# U.net
KiCad netlist of a schematic drawn in EAGLE
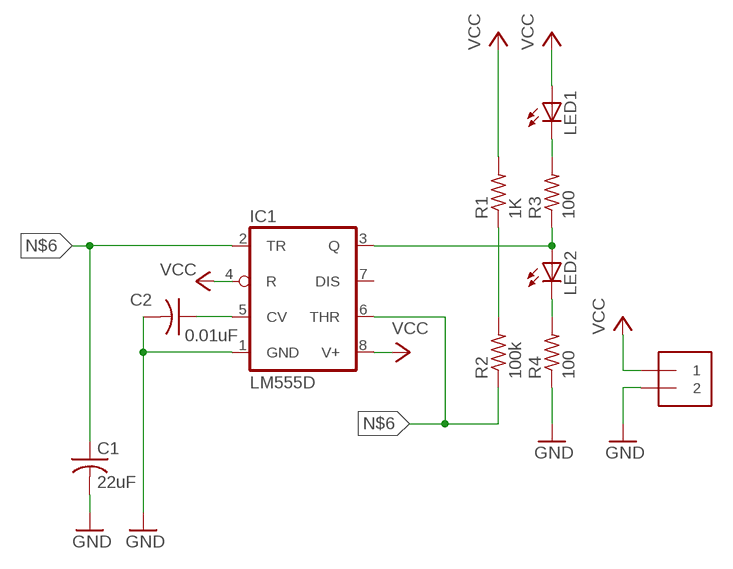
[diagram p0: schematic, sheet 1]

(export (version "E")
  (design (tool "Eeschema 10.0.6"))
  (components
    (comp (ref "C1")
      (value "22uF")
      (footprint "eagle-import:C0805")
      (libsource (lib "eagle-import") (part "C-USC0805"))
    )
    (comp (ref "C2")
      (value "0.01uF")
      (footprint "eagle-import:C0805")
      (libsource (lib "eagle-import") (part "C-USC0805"))
    )
    (comp (ref "IC1")
      (value "LM555D")
      (footprint "eagle-import:SO08")
      (libsource (lib "eagle-import") (part "555DLM"))
    )
    (comp (ref "J1")
      (value "1X2-3.5MM")
      (footprint "eagle-import:1X2-3.5MM")
      (libsource (lib "eagle-import") (part "1X2-3.5MM"))
    )
    (comp (ref "LED1")
      (value "LEDCHIPLED_0805")
      (footprint "eagle-import:CHIPLED_0805")
      (libsource (lib "eagle-import") (part "LEDCHIPLED_0805"))
    )
    (comp (ref "LED2")
      (value "LEDCHIPLED_0805")
      (footprint "eagle-import:CHIPLED_0805")
      (libsource (lib "eagle-import") (part "LEDCHIPLED_0805"))
    )
    (comp (ref "R1")
      (value "1K")
      (footprint "eagle-import:R0805")
      (libsource (lib "eagle-import") (part "R-US_R0805"))
    )
    (comp (ref "R2")
      (value "100k")
      (footprint "eagle-import:R0805")
      (libsource (lib "eagle-import") (part "R-US_R0805"))
    )
    (comp (ref "R3")
      (value "100")
      (footprint "eagle-import:R0805")
      (libsource (lib "eagle-import") (part "R-US_R0805"))
    )
    (comp (ref "R4")
      (value "100")
      (footprint "eagle-import:R0805")
      (libsource (lib "eagle-import") (part "R-US_R0805"))
    )
  )
  (nets
    (net (code "1") (name "GND") (class "Default")
      (node (ref "C1") (pin "2") (pinfunction "2_2") (pintype "passive"))
      (node (ref "C2") (pin "2") (pinfunction "2_2") (pintype "passive"))
      (node (ref "IC1") (pin "1") (pinfunction "GND_1") (pintype "power_in"))
      (node (ref "J1") (pin "2") (pinfunction "2_2") (pintype "passive"))
      (node (ref "R4") (pin "1") (pinfunction "1_1") (pintype "passive"))
    )
    (net (code "2") (name "N$6") (class "Default")
      (node (ref "C1") (pin "1") (pinfunction "1_1") (pintype "passive"))
      (node (ref "IC1") (pin "2") (pinfunction "TR_2") (pintype "input"))
      (node (ref "IC1") (pin "6") (pinfunction "THR_6") (pintype "input"))
      (node (ref "R2") (pin "1") (pinfunction "1_1") (pintype "passive"))
    )
    (net (code "3") (name "Net-(IC1-CV)") (class "Default")
      (node (ref "C2") (pin "1") (pinfunction "1_1") (pintype "passive"))
      (node (ref "IC1") (pin "5") (pinfunction "CV_5") (pintype "input"))
    )
    (net (code "4") (name "Net-(IC1-Q)") (class "Default")
      (node (ref "IC1") (pin "3") (pinfunction "Q_3") (pintype "output"))
      (node (ref "LED2") (pin "A") (pinfunction "A_A") (pintype "passive"))
      (node (ref "R3") (pin "1") (pinfunction "1_1") (pintype "passive"))
    )
    (net (code "5") (name "Net-(LED1-PadC)") (class "Default")
      (node (ref "LED1") (pin "C") (pinfunction "C_C") (pintype "passive"))
      (node (ref "R3") (pin "2") (pinfunction "2_2") (pintype "passive"))
    )
    (net (code "6") (name "Net-(LED2-PadC)") (class "Default")
      (node (ref "LED2") (pin "C") (pinfunction "C_C") (pintype "passive"))
      (node (ref "R4") (pin "2") (pinfunction "2_2") (pintype "passive"))
    )
    (net (code "7") (name "Net-(R1-Pad1)") (class "Default")
      (node (ref "R1") (pin "1") (pinfunction "1_1") (pintype "passive"))
      (node (ref "R2") (pin "2") (pinfunction "2_2") (pintype "passive"))
    )
    (net (code "8") (name "VCC") (class "Default")
      (node (ref "IC1") (pin "4") (pinfunction "R_4") (pintype "input"))
      (node (ref "IC1") (pin "8") (pinfunction "V+_8") (pintype "power_in"))
      (node (ref "J1") (pin "1") (pinfunction "1_1") (pintype "passive"))
      (node (ref "LED1") (pin "A") (pinfunction "A_A") (pintype "passive"))
      (node (ref "R1") (pin "2") (pinfunction "2_2") (pintype "passive"))
    )
    (net (code "9") (name "unconnected-(IC1-DIS-Pad7)") (class "Default")
      (node (ref "IC1") (pin "7") (pinfunction "DIS_7") (pintype "input"))
    )
  )
)
